# USB_Type_C_Connector_ESD.net
KiCad netlist of a schematic drawn in Altium Designer
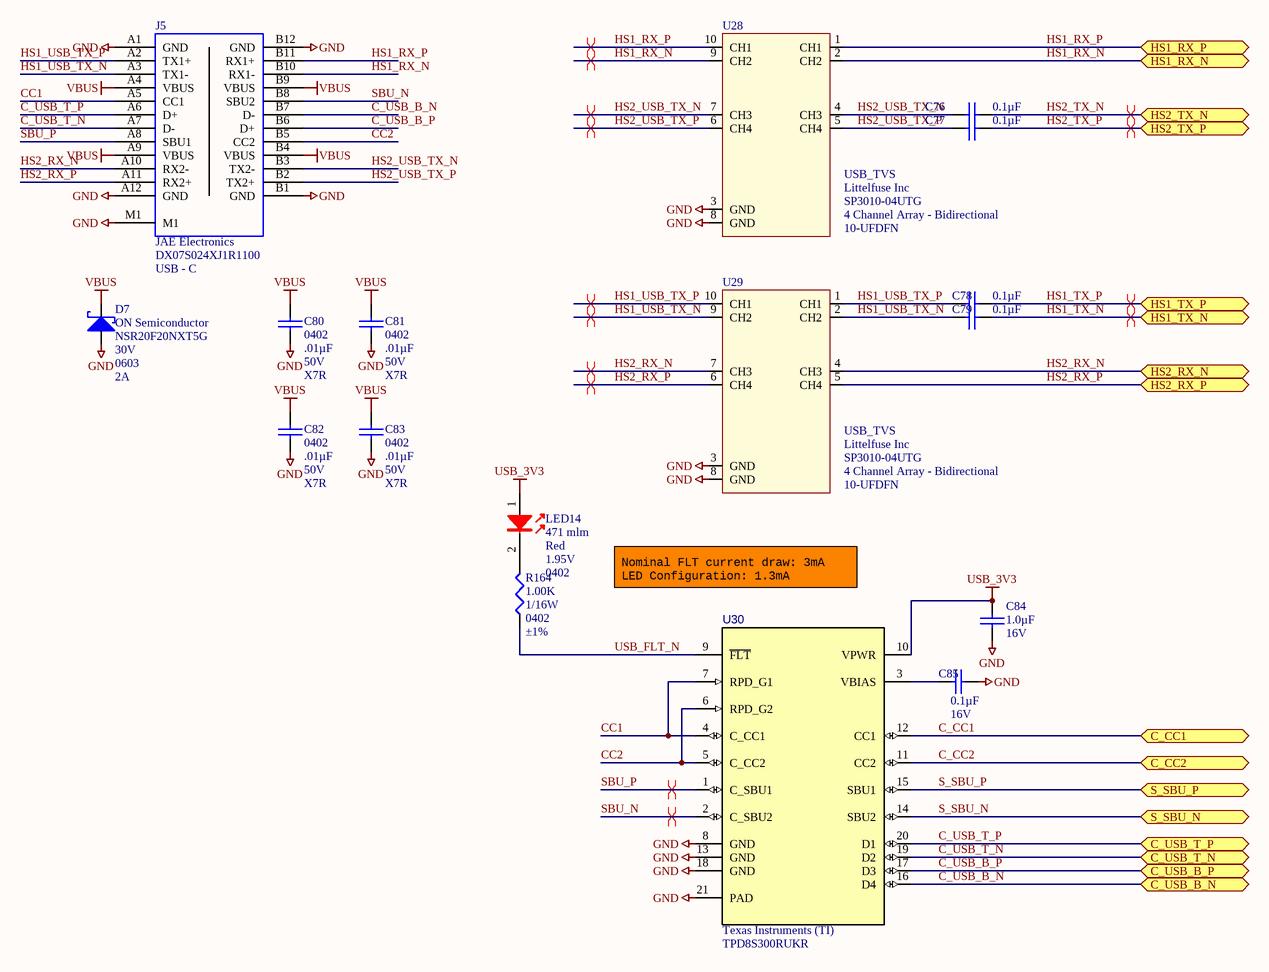
[diagram p0: USB Type C Connector ESD.SchDoc]

(export (version "E")
  (design (tool "Eeschema 10.0.6"))
  (components
    (comp (ref "C76")
      (value "0.1UF")
      (footprint "CAPC0201")
      (description "CAP CER 0.1UF 6.3V 10% X5R 0201")
      (fields
        (field (name "MANUFACTURER") "TDK Corporation")
        (field (name "MANUFACTURER PART NUMBER") "C0603X5R0J104M")
        (field (name "CAPACITANCE") "0.1µF")
      )
      (libsource (lib "Main Library") (part "C_0201_0.1UF"))
    )
    (comp (ref "C77")
      (value "0.1UF")
      (footprint "CAPC0201")
      (description "CAP CER 0.1UF 6.3V 10% X5R 0201")
      (fields
        (field (name "MANUFACTURER") "TDK Corporation")
        (field (name "MANUFACTURER PART NUMBER") "C0603X5R0J104M")
        (field (name "CAPACITANCE") "0.1µF")
      )
      (libsource (lib "Main Library") (part "C_0201_0.1UF"))
    )
    (comp (ref "C78")
      (value "0.1UF")
      (footprint "CAPC0201")
      (description "CAP CER 0.1UF 6.3V 10% X5R 0201")
      (fields
        (field (name "MANUFACTURER") "TDK Corporation")
        (field (name "MANUFACTURER PART NUMBER") "C0603X5R0J104M")
        (field (name "CAPACITANCE") "0.1µF")
      )
      (libsource (lib "Main Library") (part "C_0201_0.1UF"))
    )
    (comp (ref "C79")
      (value "0.1UF")
      (footprint "CAPC0201")
      (description "CAP CER 0.1UF 6.3V 10% X5R 0201")
      (fields
        (field (name "MANUFACTURER") "TDK Corporation")
        (field (name "MANUFACTURER PART NUMBER") "C0603X5R0J104M")
        (field (name "CAPACITANCE") "0.1µF")
      )
      (libsource (lib "Main Library") (part "C_0201_0.1UF"))
    )
    (comp (ref "C80")
      (value "10000pF")
      (footprint "C_ERA-0402")
      (description "CAP CERAMIC .01UF 50V X7R 0402")
      (fields
        (field (name "MANUFACTURER") "Murata Electronics North America")
        (field (name "MANUFACTURER PART NUMBER") "GRM155R71H103KA88D")
        (field (name "PACKAGE / CASE") "0402")
        (field (name "CAPACITANCE") ".01µF")
        (field (name "VOLTAGE - RATED") "50V")
        (field (name "TEMPERATURE COEFFICIENT") "X7R")
      )
      (libsource (lib "Main Library") (part "C_0402_10000PF_50V"))
    )
    (comp (ref "C81")
      (value "10000pF")
      (footprint "C_ERA-0402")
      (description "CAP CERAMIC .01UF 50V X7R 0402")
      (fields
        (field (name "MANUFACTURER") "Murata Electronics North America")
        (field (name "MANUFACTURER PART NUMBER") "GRM155R71H103KA88D")
        (field (name "PACKAGE / CASE") "0402")
        (field (name "CAPACITANCE") ".01µF")
        (field (name "VOLTAGE - RATED") "50V")
        (field (name "TEMPERATURE COEFFICIENT") "X7R")
      )
      (libsource (lib "Main Library") (part "C_0402_10000PF_50V"))
    )
    (comp (ref "C82")
      (value "10000pF")
      (footprint "C_ERA-0402")
      (description "CAP CERAMIC .01UF 50V X7R 0402")
      (fields
        (field (name "MANUFACTURER") "Murata Electronics North America")
        (field (name "MANUFACTURER PART NUMBER") "GRM155R71H103KA88D")
        (field (name "PACKAGE / CASE") "0402")
        (field (name "CAPACITANCE") ".01µF")
        (field (name "VOLTAGE - RATED") "50V")
        (field (name "TEMPERATURE COEFFICIENT") "X7R")
      )
      (libsource (lib "Main Library") (part "C_0402_10000PF_50V"))
    )
    (comp (ref "C83")
      (value "10000pF")
      (footprint "C_ERA-0402")
      (description "CAP CERAMIC .01UF 50V X7R 0402")
      (fields
        (field (name "MANUFACTURER") "Murata Electronics North America")
        (field (name "MANUFACTURER PART NUMBER") "GRM155R71H103KA88D")
        (field (name "PACKAGE / CASE") "0402")
        (field (name "CAPACITANCE") ".01µF")
        (field (name "VOLTAGE - RATED") "50V")
        (field (name "TEMPERATURE COEFFICIENT") "X7R")
      )
      (libsource (lib "Main Library") (part "C_0402_10000PF_50V"))
    )
    (comp (ref "C84")
      (value "1.0uF")
      (footprint "C_ERA-0402")
      (description "CAP CER 1.0UF 16V X5R 0402")
      (fields
        (field (name "MANUFACTURER") "TDK Corporation")
        (field (name "MANUFACTURER PART NUMBER") "C1005X5R1C105K050BC")
        (field (name "CAPACITANCE") "1.0µF")
        (field (name "VOLTAGE - RATED") "16V")
      )
      (libsource (lib "Main Library") (part "C_0402_1.0UF_16V"))
    )
    (comp (ref "C85")
      (value "0.1uF")
      (footprint "C_0402")
      (description "CAP CER .10UF 16V X7R 0402")
      (fields
        (field (name "MANUFACTURER") "TDK Corporation")
        (field (name "MANUFACTURER PART NUMBER") "C1005X7R1C104K050BC")
        (field (name "CAPACITANCE") "0.1µF")
        (field (name "VOLTAGE - RATED") "16V")
      )
      (libsource (lib "Main Library") (part "C_0402_0.1UF_16V"))
    )
    (comp (ref "D7")
      (value "D_SCHOTT_30V_2A_XDFN")
      (footprint "DSN2_0603")
      (description "Diode Schottky 30V 2A (DC) Surface Mount 2-DSN (1.6x.80)")
      (fields
        (field (name "REVERSE VOLTAGE (DC)") "30V")
        (field (name "MANUFACTURER") "ON Semiconductor")
        (field (name "MANUFACTURER PART NUMBER") "NSR20F20NXT5G")
        (field (name "CASE/PACKAGE") "0603")
        (field (name "AVERAGE RECTIFIED CURRENT") "2A")
      )
      (libsource (lib "Cospan Design") (part "D_SCHOTT_30V_2A_XDFN"))
    )
    (comp (ref "J5")
      (value "J_DX07S024XJ1R1100")
      (footprint "DX07S024XJ1R1100")
      (description "CONN RCPT USB C TOP MNT HYBRID")
      (fields
        (field (name "MANUFACTURER") "JAE Electronics")
        (field (name "MANUFACTURER PART NUMBER") "DX07S024XJ1R1100")
        (field (name "CONNECTOR TYPE") "USB - C")
      )
      (libsource (lib "Cospan Design") (part "J_DX07S024XJ1R1100"))
    )
    (comp (ref "LED14")
      (value "LED_RED_0402")
      (footprint "DIOM1005X07L_RED")
      (description "LED 1X0.5MM 630NM RD WTR CLR SMD")
      (fields
        (field (name "MANUFACTURER") "Kingbright Corp")
        (field (name "MANUFACTURER PART NUMBER") "APHHS1005SURCK")
        (field (name "LUMINOUS FLUX @ CURRENT - TEST") "471 mlm")
        (field (name "COLOR") "Red")
        (field (name "VOLTAGE - FORWARD (VF) TYP") "1.95V")
        (field (name "PACKAGE / CASE") "0402")
      )
      (libsource (lib "Main Library") (part "LED_RED_0402"))
    )
    (comp (ref "R164")
      (value "1.0k Ohms")
      (footprint "R_0402")
      (description "RES 1.00K OHM 1/16W 1% 0402 SMD")
      (fields
        (field (name "MANUFACTURER") "Yageo")
        (field (name "MANUFACTURER PART NUMBER") "RC0402FR-071KL")
        (field (name "RESISTANCE IN OHMS") "1.00K")
        (field (name "POWER (WATTS)") "1/16W")
        (field (name "CASE") "0402")
        (field (name "TOLERANCE") "±1%")
      )
      (libsource (lib "Main Library") (part "R_0402_1.0K"))
    )
    (comp (ref "U28")
      (value "USB_TVS")
      (footprint "TVS_DIODE_USB3.0-10")
      (description "TVS ARRAY ESD 4CH .45PF 8KV UDFN")
      (fields
        (field (name "MANUFACTURER") "Littelfuse Inc")
        (field (name "MANUFACTURER PART NUMBER") "SP3010-04UTG")
        (field (name "POLARIZATION") "4 Channel Array - Bidirectional")
        (field (name "PACKAGE / CASE") "10-UFDFN")
      )
      (libsource (lib "Main LibraryX") (part "U_SP3010-04UTG"))
    )
    (comp (ref "U29")
      (value "USB_TVS")
      (footprint "TVS_DIODE_USB3.0-10")
      (description "TVS ARRAY ESD 4CH .45PF 8KV UDFN")
      (fields
        (field (name "MANUFACTURER") "Littelfuse Inc")
        (field (name "MANUFACTURER PART NUMBER") "SP3010-04UTG")
        (field (name "POLARIZATION") "4 Channel Array - Bidirectional")
        (field (name "PACKAGE / CASE") "10-UFDFN")
      )
      (libsource (lib "Main LibraryX") (part "U_SP3010-04UTG"))
    )
    (comp (ref "U30")
      (value "U_TPD8S300RUK")
      (footprint "RUK0020B")
      (fields
        (field (name "MANUFACTURER") "Texas Instruments (TI)")
        (field (name "MANUFACTURER PART NUMBER") "TPD8S300RUKR")
      )
      (libsource (lib "Cospan Design") (part "U_TPD8S300RUK"))
    )
  )
  (nets
    (net (code "1") (name "/CC1") (class "Default")
      (node (ref "J5") (pin "A5") (pinfunction "CC1_A5") (pintype "passive"))
      (node (ref "U30") (pin "4") (pinfunction "C_CC1_4") (pintype "bidirectional"))
      (node (ref "U30") (pin "7") (pinfunction "RPD_G1_7") (pintype "input"))
    )
    (net (code "2") (name "/CC2") (class "Default")
      (node (ref "J5") (pin "B5") (pinfunction "CC2_B5") (pintype "passive"))
      (node (ref "U30") (pin "5") (pinfunction "C_CC2_5") (pintype "bidirectional"))
      (node (ref "U30") (pin "6") (pinfunction "RPD_G2_6") (pintype "input"))
    )
    (net (code "3") (name "/C_CC1") (class "Default")
      (node (ref "U30") (pin "12") (pinfunction "CC1_12") (pintype "bidirectional"))
    )
    (net (code "4") (name "/C_CC2") (class "Default")
      (node (ref "U30") (pin "11") (pinfunction "CC2_11") (pintype "bidirectional"))
    )
    (net (code "5") (name "/C_USB_B_N") (class "Default")
      (node (ref "J5") (pin "B7") (pinfunction "D-_B7") (pintype "passive"))
      (node (ref "U30") (pin "16") (pinfunction "D4_16") (pintype "bidirectional"))
    )
    (net (code "6") (name "/C_USB_B_P") (class "Default")
      (node (ref "J5") (pin "B6") (pinfunction "D+_B6") (pintype "passive"))
      (node (ref "U30") (pin "17") (pinfunction "D3_17") (pintype "bidirectional"))
    )
    (net (code "7") (name "/C_USB_T_N") (class "Default")
      (node (ref "J5") (pin "A7") (pinfunction "D-_A7") (pintype "passive"))
      (node (ref "U30") (pin "19") (pinfunction "D2_19") (pintype "bidirectional"))
    )
    (net (code "8") (name "/C_USB_T_P") (class "Default")
      (node (ref "J5") (pin "A6") (pinfunction "D+_A6") (pintype "passive"))
      (node (ref "U30") (pin "20") (pinfunction "D1_20") (pintype "bidirectional"))
    )
    (net (code "9") (name "/HS1_RX_N") (class "Default")
      (node (ref "J5") (pin "B10") (pinfunction "RX1-_B10") (pintype "passive"))
      (node (ref "U28") (pin "2") (pinfunction "CH2_2") (pintype "passive"))
      (node (ref "U28") (pin "9") (pinfunction "CH2_9") (pintype "passive"))
    )
    (net (code "10") (name "/HS1_RX_P") (class "Default")
      (node (ref "J5") (pin "B11") (pinfunction "RX1+_B11") (pintype "passive"))
      (node (ref "U28") (pin "1") (pinfunction "CH1_1") (pintype "passive"))
      (node (ref "U28") (pin "10") (pinfunction "CH1_10") (pintype "passive"))
    )
    (net (code "11") (name "/HS1_TX_N") (class "Default")
      (node (ref "C79") (pin "2") (pinfunction "2_2") (pintype "passive"))
    )
    (net (code "12") (name "/HS1_TX_P") (class "Default")
      (node (ref "C78") (pin "2") (pinfunction "2_2") (pintype "passive"))
    )
    (net (code "13") (name "/HS1_USB_TX_N") (class "Default")
      (node (ref "C79") (pin "1") (pinfunction "1_1") (pintype "passive"))
      (node (ref "J5") (pin "A3") (pinfunction "TX1-_A3") (pintype "passive"))
      (node (ref "U29") (pin "2") (pinfunction "CH2_2") (pintype "passive"))
      (node (ref "U29") (pin "9") (pinfunction "CH2_9") (pintype "passive"))
    )
    (net (code "14") (name "/HS1_USB_TX_P") (class "Default")
      (node (ref "C78") (pin "1") (pinfunction "1_1") (pintype "passive"))
      (node (ref "J5") (pin "A2") (pinfunction "TX1+_A2") (pintype "passive"))
      (node (ref "U29") (pin "1") (pinfunction "CH1_1") (pintype "passive"))
      (node (ref "U29") (pin "10") (pinfunction "CH1_10") (pintype "passive"))
    )
    (net (code "15") (name "/HS2_RX_N") (class "Default")
      (node (ref "J5") (pin "A10") (pinfunction "RX2-_A10") (pintype "passive"))
      (node (ref "U29") (pin "4") (pinfunction "CH3_4") (pintype "passive"))
      (node (ref "U29") (pin "7") (pinfunction "CH3_7") (pintype "passive"))
    )
    (net (code "16") (name "/HS2_RX_P") (class "Default")
      (node (ref "J5") (pin "A11") (pinfunction "RX2+_A11") (pintype "passive"))
      (node (ref "U29") (pin "5") (pinfunction "CH4_5") (pintype "passive"))
      (node (ref "U29") (pin "6") (pinfunction "CH4_6") (pintype "passive"))
    )
    (net (code "17") (name "/HS2_TX_N") (class "Default")
      (node (ref "C76") (pin "2") (pinfunction "2_2") (pintype "passive"))
    )
    (net (code "18") (name "/HS2_TX_P") (class "Default")
      (node (ref "C77") (pin "2") (pinfunction "2_2") (pintype "passive"))
    )
    (net (code "19") (name "/HS2_USB_TX_N") (class "Default")
      (node (ref "C76") (pin "1") (pinfunction "1_1") (pintype "passive"))
      (node (ref "J5") (pin "B3") (pinfunction "TX2-_B3") (pintype "passive"))
      (node (ref "U28") (pin "4") (pinfunction "CH3_4") (pintype "passive"))
      (node (ref "U28") (pin "7") (pinfunction "CH3_7") (pintype "passive"))
    )
    (net (code "20") (name "/HS2_USB_TX_P") (class "Default")
      (node (ref "C77") (pin "1") (pinfunction "1_1") (pintype "passive"))
      (node (ref "J5") (pin "B2") (pinfunction "TX2+_B2") (pintype "passive"))
      (node (ref "U28") (pin "5") (pinfunction "CH4_5") (pintype "passive"))
      (node (ref "U28") (pin "6") (pinfunction "CH4_6") (pintype "passive"))
    )
    (net (code "21") (name "/SBU_N") (class "Default")
      (node (ref "J5") (pin "B8") (pinfunction "SBU2_B8") (pintype "passive"))
      (node (ref "U30") (pin "2") (pinfunction "C_SBU2_2") (pintype "bidirectional"))
    )
    (net (code "22") (name "/SBU_P") (class "Default")
      (node (ref "J5") (pin "A8") (pinfunction "SBU1_A8") (pintype "passive"))
      (node (ref "U30") (pin "1") (pinfunction "C_SBU1_1") (pintype "bidirectional"))
    )
    (net (code "23") (name "/S_SBU_N") (class "Default")
      (node (ref "U30") (pin "14") (pinfunction "SBU2_14") (pintype "bidirectional"))
    )
    (net (code "24") (name "/S_SBU_P") (class "Default")
      (node (ref "U30") (pin "15") (pinfunction "SBU1_15") (pintype "bidirectional"))
    )
    (net (code "25") (name "/USB_FLT_N") (class "Default")
      (node (ref "R164") (pin "2") (pinfunction "2_2") (pintype "passive"))
      (node (ref "U30") (pin "9") (pinfunction "FLT_9") (pintype "open_collector"))
    )
    (net (code "26") (name "GND") (class "Default")
      (node (ref "C80") (pin "1") (pinfunction "1_1") (pintype "passive"))
      (node (ref "C81") (pin "1") (pinfunction "1_1") (pintype "passive"))
      (node (ref "C82") (pin "1") (pinfunction "1_1") (pintype "passive"))
      (node (ref "C83") (pin "1") (pinfunction "1_1") (pintype "passive"))
      (node (ref "C84") (pin "1") (pinfunction "1_1") (pintype "passive"))
      (node (ref "C85") (pin "1") (pinfunction "1_1") (pintype "passive"))
      (node (ref "D7") (pin "A") (pinfunction "A_A") (pintype "passive"))
      (node (ref "J5") (pin "A1") (pinfunction "GND_A1") (pintype "passive"))
      (node (ref "J5") (pin "A12") (pinfunction "GND_A12") (pintype "passive"))
      (node (ref "J5") (pin "B1") (pinfunction "GND_B1") (pintype "passive"))
      (node (ref "J5") (pin "B12") (pinfunction "GND_B12") (pintype "passive"))
      (node (ref "J5") (pin "M1") (pinfunction "M1_M1") (pintype "passive"))
      (node (ref "U28") (pin "3") (pinfunction "GND_3") (pintype "passive"))
      (node (ref "U28") (pin "8") (pinfunction "GND_8") (pintype "passive"))
      (node (ref "U29") (pin "3") (pinfunction "GND_3") (pintype "passive"))
      (node (ref "U29") (pin "8") (pinfunction "GND_8") (pintype "passive"))
      (node (ref "U30") (pin "13") (pinfunction "GND_13") (pintype "power_in"))
      (node (ref "U30") (pin "18") (pinfunction "GND_18") (pintype "power_in"))
      (node (ref "U30") (pin "21") (pinfunction "PAD_21") (pintype "power_in"))
      (node (ref "U30") (pin "8") (pinfunction "GND_8") (pintype "power_in"))
    )
    (net (code "27") (name "Net-(LED14-Pad2)") (class "Default")
      (node (ref "LED14") (pin "2") (pinfunction "2_2") (pintype "passive"))
      (node (ref "R164") (pin "1") (pinfunction "1_1") (pintype "passive"))
    )
    (net (code "28") (name "Net-(U30-VBIAS)") (class "Default")
      (node (ref "C85") (pin "2") (pinfunction "2_2") (pintype "passive"))
      (node (ref "U30") (pin "3") (pinfunction "VBIAS_3") (pintype "power_in"))
    )
    (net (code "29") (name "USB_3V3") (class "Default")
      (node (ref "C84") (pin "2") (pinfunction "2_2") (pintype "passive"))
      (node (ref "LED14") (pin "1") (pinfunction "1_1") (pintype "passive"))
      (node (ref "U30") (pin "10") (pinfunction "VPWR_10") (pintype "power_in"))
    )
    (net (code "30") (name "VBUS") (class "Default")
      (node (ref "C80") (pin "2") (pinfunction "2_2") (pintype "passive"))
      (node (ref "C81") (pin "2") (pinfunction "2_2") (pintype "passive"))
      (node (ref "C82") (pin "2") (pinfunction "2_2") (pintype "passive"))
      (node (ref "C83") (pin "2") (pinfunction "2_2") (pintype "passive"))
      (node (ref "D7") (pin "C") (pinfunction "C_C") (pintype "passive"))
      (node (ref "J5") (pin "A4") (pinfunction "VBUS_A4") (pintype "passive"))
      (node (ref "J5") (pin "A9") (pinfunction "VBUS_A9") (pintype "passive"))
      (node (ref "J5") (pin "B4") (pinfunction "VBUS_B4") (pintype "passive"))
      (node (ref "J5") (pin "B9") (pinfunction "VBUS_B9") (pintype "passive"))
    )
  )
)
